# 555circuit.net
KiCad netlist of a schematic drawn in EAGLE
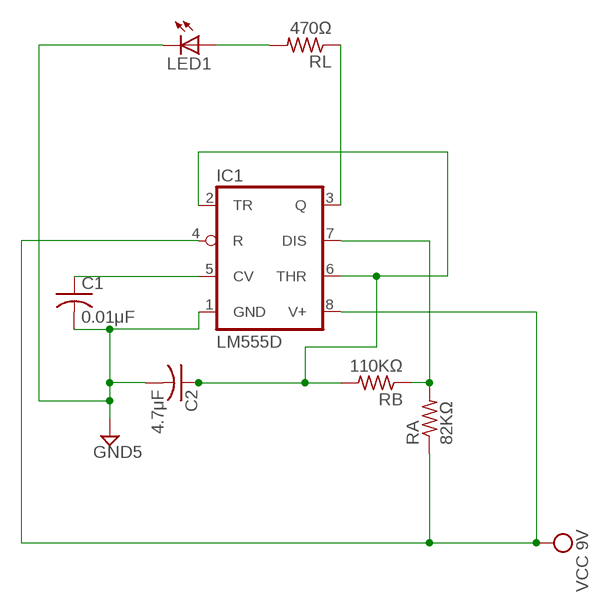
[diagram p0: schematic, sheet 1]

(export (version "E")
  (design (tool "Eeschema 10.0.6"))
  (components
    (comp (ref "C1")
      (value "0.01μF")
      (footprint "eagle-import:C025-024X044")
      (libsource (lib "eagle-import") (part "C-US025-024X044"))
    )
    (comp (ref "C2")
      (value "4.7μF")
      (footprint "eagle-import:C025-024X044")
      (libsource (lib "eagle-import") (part "C-US025-024X044"))
    )
    (comp (ref "IC1")
      (value "LM555D")
      (footprint "eagle-import:SO08")
      (libsource (lib "eagle-import") (part "555DLM"))
    )
    (comp (ref "LED1")
      (value "LED")
      (footprint "eagle-import:SMARTLED-TTW")
      (libsource (lib "eagle-import") (part "LED"))
    )
    (comp (ref "RA")
      (value "82KΩ")
      (footprint "eagle-import:0204V")
      (libsource (lib "eagle-import") (part "R-US_0204/2V"))
    )
    (comp (ref "RB")
      (value "110KΩ")
      (footprint "eagle-import:0204V")
      (libsource (lib "eagle-import") (part "R-US_0204/2V"))
    )
    (comp (ref "RL")
      (value "470Ω")
      (footprint "eagle-import:0204V")
      (libsource (lib "eagle-import") (part "R-US_0204/2V"))
    )
  )
  (nets
    (net (code "1") (name "GND5") (class "Default")
      (node (ref "C1") (pin "2") (pinfunction "2_2") (pintype "passive"))
      (node (ref "C2") (pin "2") (pinfunction "2_2") (pintype "passive"))
      (node (ref "IC1") (pin "1") (pinfunction "GND_1") (pintype "power_in"))
      (node (ref "LED1") (pin "C@1") (pinfunction "C_C@1") (pintype "passive"))
    )
    (net (code "2") (name "Net-(IC1-CV)") (class "Default")
      (node (ref "C1") (pin "1") (pinfunction "1_1") (pintype "passive"))
      (node (ref "IC1") (pin "5") (pinfunction "CV_5") (pintype "input"))
    )
    (net (code "3") (name "Net-(IC1-DIS)") (class "Default")
      (node (ref "IC1") (pin "7") (pinfunction "DIS_7") (pintype "input"))
      (node (ref "RA") (pin "2") (pinfunction "2_2") (pintype "passive"))
      (node (ref "RB") (pin "1") (pinfunction "1_1") (pintype "passive"))
    )
    (net (code "4") (name "Net-(IC1-Q)") (class "Default")
      (node (ref "IC1") (pin "3") (pinfunction "Q_3") (pintype "output"))
      (node (ref "RL") (pin "1") (pinfunction "1_1") (pintype "passive"))
    )
    (net (code "5") (name "Net-(IC1-THR)") (class "Default")
      (node (ref "C2") (pin "1") (pinfunction "1_1") (pintype "passive"))
      (node (ref "IC1") (pin "2") (pinfunction "TR_2") (pintype "input"))
      (node (ref "IC1") (pin "6") (pinfunction "THR_6") (pintype "input"))
      (node (ref "RB") (pin "2") (pinfunction "2_2") (pintype "passive"))
    )
    (net (code "6") (name "Net-(LED1-A)") (class "Default")
      (node (ref "LED1") (pin "A@1") (pinfunction "A_A@1") (pintype "passive"))
      (node (ref "RL") (pin "2") (pinfunction "2_2") (pintype "passive"))
    )
    (net (code "7") (name "VCC 9V") (class "Default")
      (node (ref "IC1") (pin "4") (pinfunction "R_4") (pintype "input"))
      (node (ref "IC1") (pin "8") (pinfunction "V+_8") (pintype "power_in"))
      (node (ref "RA") (pin "1") (pinfunction "1_1") (pintype "passive"))
    )
  )
)
